# schematic.net
KiCad netlist of a schematic drawn in EAGLE
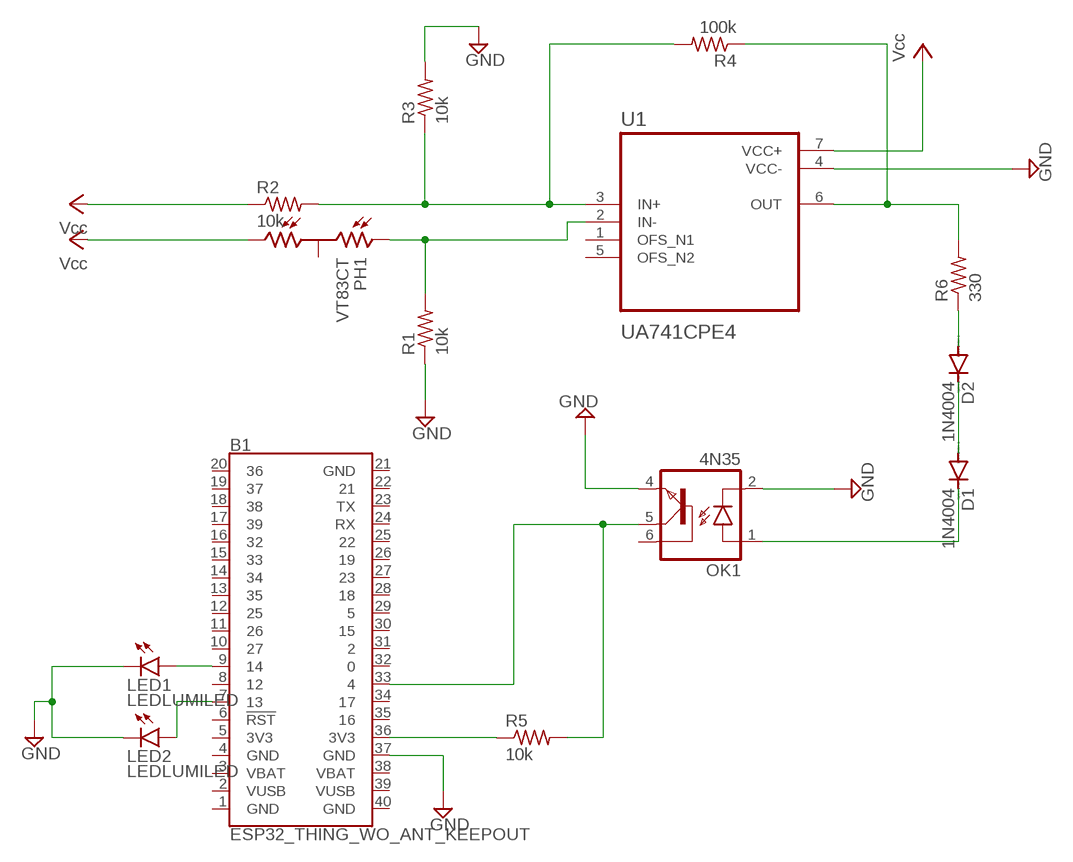
[diagram p0: schematic, sheet 1]

(export (version "E")
  (design (tool "Eeschema 10.0.6"))
  (components
    (comp (ref "B1")
      (value "ESP32_THING_WO_ANT_KEEPOUT")
      (footprint "eagle-import:ESP32_THING_NO_ANT")
      (libsource (lib "eagle-import") (part "ESP32_THING_WO_ANT_KEEPOUT"))
    )
    (comp (ref "D1")
      (value "1N4004")
      (footprint "eagle-import:DO41-10")
      (libsource (lib "eagle-import") (part "1N4004"))
    )
    (comp (ref "D2")
      (value "1N4004")
      (footprint "eagle-import:DO41-10")
      (libsource (lib "eagle-import") (part "1N4004"))
    )
    (comp (ref "LED1")
      (value "LEDLUMILED")
      (footprint "eagle-import:LUMILED")
      (libsource (lib "eagle-import") (part "LEDLUMILED"))
    )
    (comp (ref "LED2")
      (value "LEDLUMILED")
      (footprint "eagle-import:LUMILED")
      (libsource (lib "eagle-import") (part "LEDLUMILED"))
    )
    (comp (ref "OK1")
      (value "4N35")
      (footprint "eagle-import:DIL06")
      (fields (field (name "MF") "FAIRCHILD SEMICONDUCTOR"))
      (libsource (lib "eagle-import") (part "4N35"))
    )
    (comp (ref "PH1")
      (value "VT83CT")
      (footprint "eagle-import:VT800CT")
      (libsource (lib "eagle-import") (part "VT83CT"))
    )
    (comp (ref "R1")
      (value "10k")
      (footprint "eagle-import:0204_7")
      (libsource (lib "eagle-import") (part "R-US_0204/7"))
    )
    (comp (ref "R2")
      (value "10k")
      (footprint "eagle-import:0204_7")
      (libsource (lib "eagle-import") (part "R-US_0204/7"))
    )
    (comp (ref "R3")
      (value "10k")
      (footprint "eagle-import:0204_7")
      (libsource (lib "eagle-import") (part "R-US_0204/7"))
    )
    (comp (ref "R4")
      (value "100k")
      (footprint "eagle-import:0204_7")
      (libsource (lib "eagle-import") (part "R-US_0204/7"))
    )
    (comp (ref "R5")
      (value "10k")
      (footprint "eagle-import:0204_7")
      (libsource (lib "eagle-import") (part "R-US_0204/7"))
    )
    (comp (ref "R6")
      (value "330")
      (footprint "eagle-import:0204_7")
      (libsource (lib "eagle-import") (part "R-US_0204/7"))
    )
    (comp (ref "U1")
      (value "UA741CPE4")
      (footprint "eagle-import:DIP794W45P254L959H508Q8")
      (fields (field (name "MF") "Texas Instruments"))
      (libsource (lib "eagle-import") (part "UA741CPE4"))
    )
  )
  (nets
    (net (code "1") (name "GND") (class "Default")
      (node (ref "B1") (pin "37") (pinfunction "GND_37") (pintype "bidirectional"))
      (node (ref "LED1") (pin "4-") (pinfunction "C_4-") (pintype "passive"))
      (node (ref "LED2") (pin "4-") (pinfunction "C_4-") (pintype "passive"))
      (node (ref "OK1") (pin "2") (pinfunction "C_2") (pintype "passive"))
      (node (ref "OK1") (pin "4") (pinfunction "EMI_4") (pintype "passive"))
      (node (ref "R1") (pin "1") (pinfunction "1_1") (pintype "passive"))
      (node (ref "R3") (pin "2") (pinfunction "2_2") (pintype "passive"))
      (node (ref "U1") (pin "4") (pinfunction "VCC-_4") (pintype "power_in"))
    )
    (net (code "2") (name "Net-(B1-3V3-Pad36)") (class "Default")
      (node (ref "B1") (pin "36") (pinfunction "3V3_36") (pintype "bidirectional"))
      (node (ref "R5") (pin "1") (pinfunction "1_1") (pintype "passive"))
    )
    (net (code "3") (name "Net-(B1-4)") (class "Default")
      (node (ref "B1") (pin "33") (pinfunction "4_33") (pintype "bidirectional"))
      (node (ref "OK1") (pin "5") (pinfunction "COL_5") (pintype "passive"))
      (node (ref "R5") (pin "2") (pinfunction "2_2") (pintype "passive"))
    )
    (net (code "4") (name "Net-(B1-13)") (class "Default")
      (node (ref "B1") (pin "7") (pinfunction "13_7") (pintype "bidirectional"))
      (node (ref "LED2") (pin "2+") (pinfunction "A_2+") (pintype "passive"))
    )
    (net (code "5") (name "Net-(B1-14)") (class "Default")
      (node (ref "B1") (pin "9") (pinfunction "14_9") (pintype "bidirectional"))
      (node (ref "LED1") (pin "2+") (pinfunction "A_2+") (pintype "passive"))
    )
    (net (code "6") (name "Net-(D1-PadA)") (class "Default")
      (node (ref "D1") (pin "A") (pinfunction "A_A") (pintype "passive"))
      (node (ref "D2") (pin "C") (pinfunction "C_C") (pintype "passive"))
    )
    (net (code "7") (name "Net-(D2-PadA)") (class "Default")
      (node (ref "D2") (pin "A") (pinfunction "A_A") (pintype "passive"))
      (node (ref "R6") (pin "1") (pinfunction "1_1") (pintype "passive"))
    )
    (net (code "8") (name "Net-(OK1-A)") (class "Default")
      (node (ref "D1") (pin "C") (pinfunction "C_C") (pintype "passive"))
      (node (ref "OK1") (pin "1") (pinfunction "A_1") (pintype "passive"))
    )
    (net (code "9") (name "Net-(U1-IN+)") (class "Default")
      (node (ref "R2") (pin "2") (pinfunction "2_2") (pintype "passive"))
      (node (ref "R3") (pin "1") (pinfunction "1_1") (pintype "passive"))
      (node (ref "R4") (pin "2") (pinfunction "2_2") (pintype "passive"))
      (node (ref "U1") (pin "3") (pinfunction "IN+_3") (pintype "input"))
    )
    (net (code "10") (name "Net-(U1-IN-)") (class "Default")
      (node (ref "PH1") (pin "1") (pinfunction "1_1") (pintype "passive"))
      (node (ref "R1") (pin "2") (pinfunction "2_2") (pintype "passive"))
      (node (ref "U1") (pin "2") (pinfunction "IN-_2") (pintype "input"))
    )
    (net (code "11") (name "Net-(U1-OUT)") (class "Default")
      (node (ref "R4") (pin "1") (pinfunction "1_1") (pintype "passive"))
      (node (ref "R6") (pin "2") (pinfunction "2_2") (pintype "passive"))
      (node (ref "U1") (pin "6") (pinfunction "OUT_6") (pintype "output"))
    )
    (net (code "12") (name "Vcc") (class "Default")
      (node (ref "PH1") (pin "3") (pinfunction "3_3") (pintype "passive"))
      (node (ref "R2") (pin "1") (pinfunction "1_1") (pintype "passive"))
      (node (ref "U1") (pin "7") (pinfunction "VCC+_7") (pintype "power_in"))
    )
    (net (code "13") (name "unconnected-(B1-0-Pad32)") (class "Default")
      (node (ref "B1") (pin "32") (pinfunction "0_32") (pintype "bidirectional"))
    )
    (net (code "14") (name "unconnected-(B1-2-Pad31)") (class "Default")
      (node (ref "B1") (pin "31") (pinfunction "2_31") (pintype "bidirectional"))
    )
    (net (code "15") (name "unconnected-(B1-3V3-Pad5)") (class "Default")
      (node (ref "B1") (pin "5") (pinfunction "3V3_5") (pintype "bidirectional"))
    )
    (net (code "16") (name "unconnected-(B1-5-Pad29)") (class "Default")
      (node (ref "B1") (pin "29") (pinfunction "5_29") (pintype "bidirectional"))
    )
    (net (code "17") (name "unconnected-(B1-12-Pad8)") (class "Default")
      (node (ref "B1") (pin "8") (pinfunction "12_8") (pintype "bidirectional"))
    )
    (net (code "18") (name "unconnected-(B1-15-Pad30)") (class "Default")
      (node (ref "B1") (pin "30") (pinfunction "15_30") (pintype "bidirectional"))
    )
    (net (code "19") (name "unconnected-(B1-16-Pad35)") (class "Default")
      (node (ref "B1") (pin "35") (pinfunction "16_35") (pintype "bidirectional"))
    )
    (net (code "20") (name "unconnected-(B1-17-Pad34)") (class "Default")
      (node (ref "B1") (pin "34") (pinfunction "17_34") (pintype "bidirectional"))
    )
    (net (code "21") (name "unconnected-(B1-18-Pad28)") (class "Default")
      (node (ref "B1") (pin "28") (pinfunction "18_28") (pintype "bidirectional"))
    )
    (net (code "22") (name "unconnected-(B1-19-Pad26)") (class "Default")
      (node (ref "B1") (pin "26") (pinfunction "19_26") (pintype "bidirectional"))
    )
    (net (code "23") (name "unconnected-(B1-21-Pad22)") (class "Default")
      (node (ref "B1") (pin "22") (pinfunction "21_22") (pintype "bidirectional"))
    )
    (net (code "24") (name "unconnected-(B1-22-Pad25)") (class "Default")
      (node (ref "B1") (pin "25") (pinfunction "22_25") (pintype "bidirectional"))
    )
    (net (code "25") (name "unconnected-(B1-23-Pad27)") (class "Default")
      (node (ref "B1") (pin "27") (pinfunction "23_27") (pintype "bidirectional"))
    )
    (net (code "26") (name "unconnected-(B1-25-Pad12)") (class "Default")
      (node (ref "B1") (pin "12") (pinfunction "25_12") (pintype "bidirectional"))
    )
    (net (code "27") (name "unconnected-(B1-26-Pad11)") (class "Default")
      (node (ref "B1") (pin "11") (pinfunction "26_11") (pintype "bidirectional"))
    )
    (net (code "28") (name "unconnected-(B1-27-Pad10)") (class "Default")
      (node (ref "B1") (pin "10") (pinfunction "27_10") (pintype "bidirectional"))
    )
    (net (code "29") (name "unconnected-(B1-32-Pad16)") (class "Default")
      (node (ref "B1") (pin "16") (pinfunction "32_16") (pintype "bidirectional"))
    )
    (net (code "30") (name "unconnected-(B1-33-Pad15)") (class "Default")
      (node (ref "B1") (pin "15") (pinfunction "33_15") (pintype "bidirectional"))
    )
    (net (code "31") (name "unconnected-(B1-34-Pad14)") (class "Default")
      (node (ref "B1") (pin "14") (pinfunction "34_14") (pintype "bidirectional"))
    )
    (net (code "32") (name "unconnected-(B1-35-Pad13)") (class "Default")
      (node (ref "B1") (pin "13") (pinfunction "35_13") (pintype "bidirectional"))
    )
    (net (code "33") (name "unconnected-(B1-36-Pad20)") (class "Default")
      (node (ref "B1") (pin "20") (pinfunction "36_20") (pintype "bidirectional"))
    )
    (net (code "34") (name "unconnected-(B1-37-Pad19)") (class "Default")
      (node (ref "B1") (pin "19") (pinfunction "37_19") (pintype "bidirectional"))
    )
    (net (code "35") (name "unconnected-(B1-38-Pad18)") (class "Default")
      (node (ref "B1") (pin "18") (pinfunction "38_18") (pintype "bidirectional"))
    )
    (net (code "36") (name "unconnected-(B1-39-Pad17)") (class "Default")
      (node (ref "B1") (pin "17") (pinfunction "39_17") (pintype "bidirectional"))
    )
    (net (code "37") (name "unconnected-(B1-GND-Pad1)") (class "Default")
      (node (ref "B1") (pin "1") (pinfunction "GND_1") (pintype "bidirectional"))
    )
    (net (code "38") (name "unconnected-(B1-GND-Pad4)") (class "Default")
      (node (ref "B1") (pin "4") (pinfunction "GND_4") (pintype "bidirectional"))
    )
    (net (code "39") (name "unconnected-(B1-GND-Pad21)") (class "Default")
      (node (ref "B1") (pin "21") (pinfunction "GND_21") (pintype "bidirectional"))
    )
    (net (code "40") (name "unconnected-(B1-GND-Pad40)") (class "Default")
      (node (ref "B1") (pin "40") (pinfunction "GND_40") (pintype "bidirectional"))
    )
    (net (code "41") (name "unconnected-(B1-RX-Pad24)") (class "Default")
      (node (ref "B1") (pin "24") (pinfunction "RX_24") (pintype "bidirectional"))
    )
    (net (code "42") (name "unconnected-(B1-TX-Pad23)") (class "Default")
      (node (ref "B1") (pin "23") (pinfunction "TX_23") (pintype "bidirectional"))
    )
    (net (code "43") (name "unconnected-(B1-VBAT-Pad3)") (class "Default")
      (node (ref "B1") (pin "3") (pinfunction "VBAT_3") (pintype "bidirectional"))
    )
    (net (code "44") (name "unconnected-(B1-VBAT-Pad38)") (class "Default")
      (node (ref "B1") (pin "38") (pinfunction "VBAT_38") (pintype "bidirectional"))
    )
    (net (code "45") (name "unconnected-(B1-VUSB-Pad2)") (class "Default")
      (node (ref "B1") (pin "2") (pinfunction "VUSB_2") (pintype "bidirectional"))
    )
    (net (code "46") (name "unconnected-(B1-VUSB-Pad39)") (class "Default")
      (node (ref "B1") (pin "39") (pinfunction "VUSB_39") (pintype "bidirectional"))
    )
    (net (code "47") (name "unconnected-(B1-~{RST}-Pad6)") (class "Default")
      (node (ref "B1") (pin "6") (pinfunction "~{RST}_6") (pintype "bidirectional"))
    )
    (net (code "48") (name "unconnected-(OK1-BAS-Pad6)") (class "Default")
      (node (ref "OK1") (pin "6") (pinfunction "BAS_6") (pintype "passive"))
    )
    (net (code "49") (name "unconnected-(PH1-Pad2)") (class "Default")
      (node (ref "PH1") (pin "2") (pinfunction "2_2") (pintype "passive"))
    )
    (net (code "50") (name "unconnected-(U1-OFS_N1-Pad1)") (class "Default")
      (node (ref "U1") (pin "1") (pinfunction "OFS_N1_1") (pintype "input"))
    )
    (net (code "51") (name "unconnected-(U1-OFS_N2-Pad5)") (class "Default")
      (node (ref "U1") (pin "5") (pinfunction "OFS_N2_5") (pintype "input"))
    )
  )
)
